# An_lisis_AC.net
KiCad netlist of a schematic drawn in Altium Designer
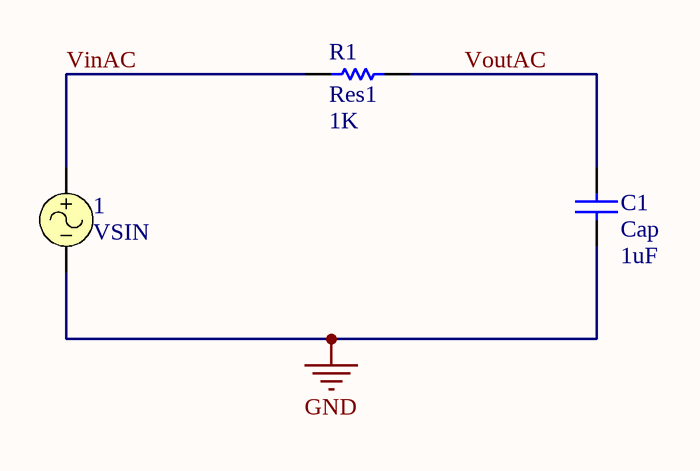
[diagram p0: Análisis AC.SchDoc]

(export (version "E")
  (design (tool "Eeschema 10.0.6"))
  (components
    (comp (ref "1")
      (value "VSIN")
      (description "Sinusoidal Voltage Source")
      (fields (field (name "PUBLISHER") "Altium Limited"))
      (libsource (lib "Simulation Sources") (part "VSIN"))
    )
    (comp (ref "C1")
      (value "Cap")
      (footprint "RAD-0.3")
      (description "Capacitor")
      (fields (field (name "ALTIUM_VALUE") "1uF") (field (name "PUBLISHER") "Altium Limited"))
      (libsource (lib "Miscellaneous Devices") (part "Cap"))
    )
    (comp (ref "R1")
      (value "Res1")
      (footprint "AXIAL-0.3")
      (description "Resistor")
      (fields (field (name "ALTIUM_VALUE") "1K") (field (name "PUBLISHER") "Altium Limited"))
      (libsource (lib "Miscellaneous Devices") (part "Res1"))
    )
  )
  (nets
    (net (code "1") (name "/VinAC") (class "Default")
      (node (ref "1") (pin "1") (pinfunction "1_1") (pintype "passive"))
      (node (ref "R1") (pin "1") (pinfunction "1_1") (pintype "passive"))
    )
    (net (code "2") (name "/VoutAC") (class "Default")
      (node (ref "C1") (pin "2") (pinfunction "2_2") (pintype "passive"))
      (node (ref "R1") (pin "2") (pinfunction "2_2") (pintype "passive"))
    )
    (net (code "3") (name "GND") (class "Default")
      (node (ref "1") (pin "2") (pinfunction "2_2") (pintype "passive"))
      (node (ref "C1") (pin "1") (pinfunction "1_1") (pintype "passive"))
    )
  )
)
